# NRF52_CTAP_Authenticator.net
KiCad netlist of a schematic drawn in EAGLE
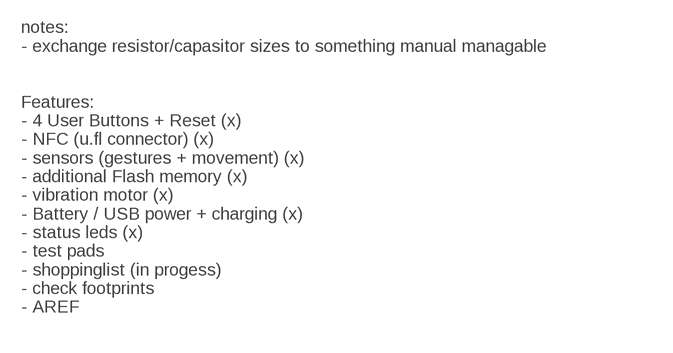
[diagram p0: schematic, sheet 1, part 1 of 2]
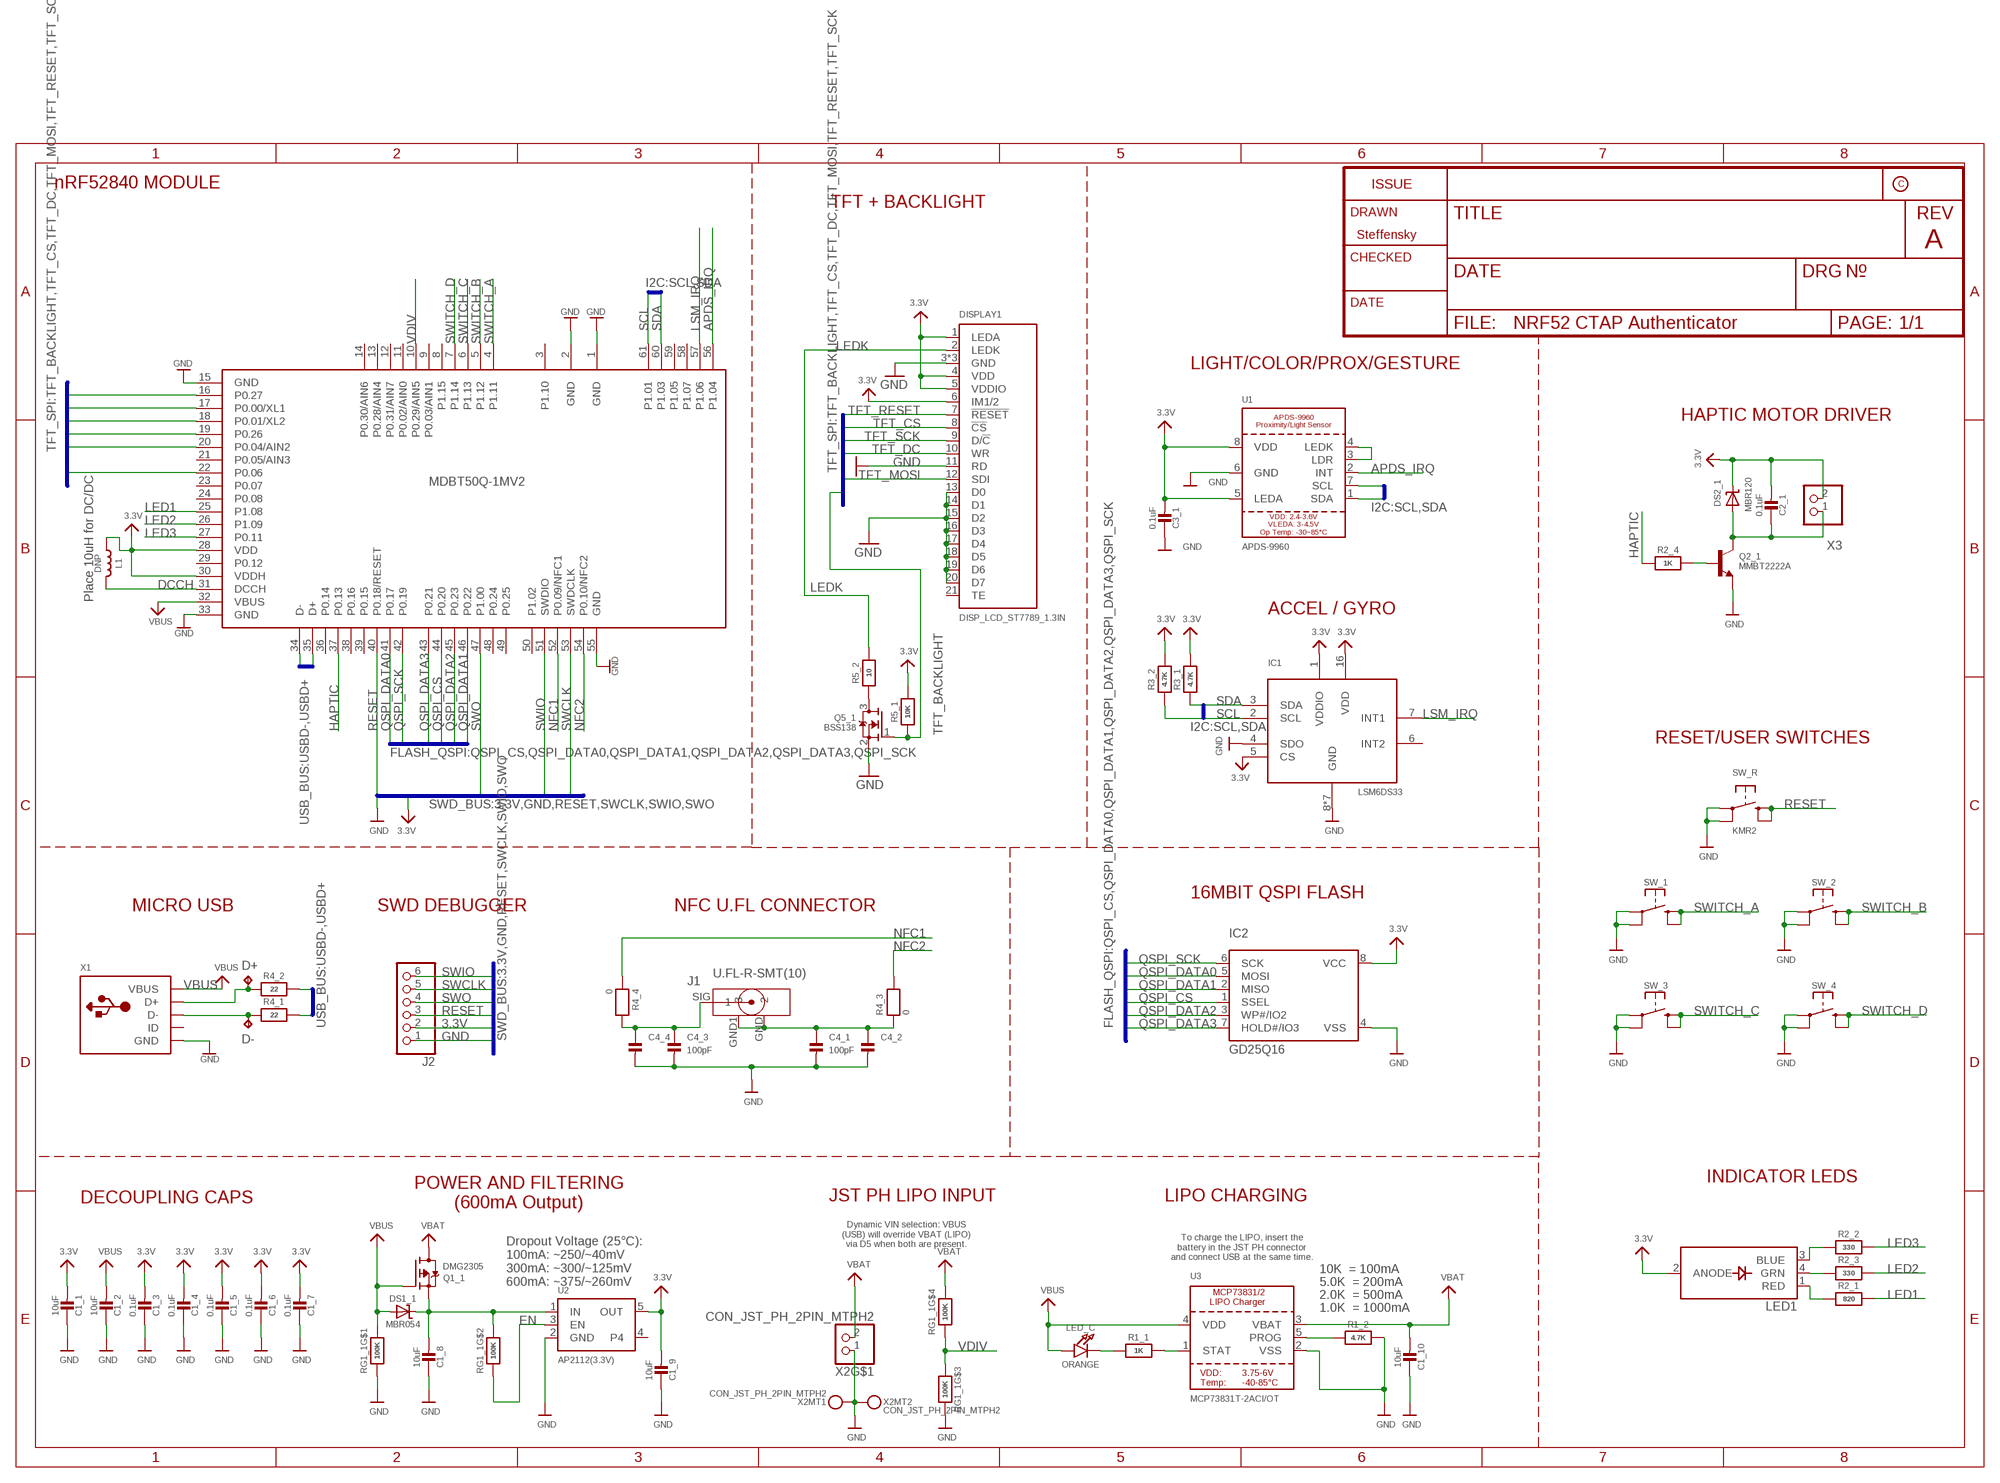
[diagram p1: schematic, sheet 1, part 2 of 2]

(export (version "E")
  (design (tool "Eeschema 10.0.6"))
  (components
    (comp (ref "C1_1")
      (value "10uF")
      (footprint "eagle-import:0805_NOTHERMALS")
      (libsource (lib "eagle-import") (part "CAP_CERAMIC0805-NOTHERMALS"))
    )
    (comp (ref "C1_2")
      (value "10uF")
      (footprint "eagle-import:0805_NOTHERMALS")
      (libsource (lib "eagle-import") (part "CAP_CERAMIC0805-NOTHERMALS"))
    )
    (comp (ref "C1_3")
      (value "0.1uF")
      (footprint "eagle-import:0805_NOTHERMALS")
      (libsource (lib "eagle-import") (part "CAP_CERAMIC0805-NOTHERMALS"))
    )
    (comp (ref "C1_4")
      (value "0.1uF")
      (footprint "eagle-import:0805_NOTHERMALS")
      (libsource (lib "eagle-import") (part "CAP_CERAMIC0805-NOTHERMALS"))
    )
    (comp (ref "C1_5")
      (value "0.1uF")
      (footprint "eagle-import:0805_NOTHERMALS")
      (libsource (lib "eagle-import") (part "CAP_CERAMIC0805-NOTHERMALS"))
    )
    (comp (ref "C1_6")
      (value "0.1uF")
      (footprint "eagle-import:0805_NOTHERMALS")
      (libsource (lib "eagle-import") (part "CAP_CERAMIC0805-NOTHERMALS"))
    )
    (comp (ref "C1_7")
      (value "0.1uF")
      (footprint "eagle-import:0805_NOTHERMALS")
      (libsource (lib "eagle-import") (part "CAP_CERAMIC0805-NOTHERMALS"))
    )
    (comp (ref "C1_8")
      (value "10uF")
      (footprint "eagle-import:0805_NOTHERMALS")
      (libsource (lib "eagle-import") (part "CAP_CERAMIC0805-NOTHERMALS"))
    )
    (comp (ref "C1_9")
      (value "10uF")
      (footprint "eagle-import:0805_NOTHERMALS")
      (libsource (lib "eagle-import") (part "CAP_CERAMIC0805-NOTHERMALS"))
    )
    (comp (ref "C1_10")
      (value "10uF")
      (footprint "eagle-import:0805_NOTHERMALS")
      (libsource (lib "eagle-import") (part "CAP_CERAMIC0805-NOTHERMALS"))
    )
    (comp (ref "C2_1")
      (value "0.1uF")
      (footprint "eagle-import:0805_NOTHERMALS")
      (libsource (lib "eagle-import") (part "CAP_CERAMIC0805-NOTHERMALS"))
    )
    (comp (ref "C3_1")
      (value "0.1uF")
      (footprint "eagle-import:0805_NOTHERMALS")
      (libsource (lib "eagle-import") (part "CAP_CERAMIC0805-NOTHERMALS"))
    )
    (comp (ref "C4_1")
      (value "100pF")
      (footprint "eagle-import:0805_NOTHERMALS")
      (libsource (lib "eagle-import") (part "CAP_CERAMIC0805-NOTHERMALS"))
    )
    (comp (ref "C4_2")
      (value "CAP_CERAMIC0805-NOTHERMALS")
      (footprint "eagle-import:0805_NOTHERMALS")
      (libsource (lib "eagle-import") (part "CAP_CERAMIC0805-NOTHERMALS"))
    )
    (comp (ref "C4_3")
      (value "100pF")
      (footprint "eagle-import:0805_NOTHERMALS")
      (libsource (lib "eagle-import") (part "CAP_CERAMIC0805-NOTHERMALS"))
    )
    (comp (ref "C4_4")
      (value "CAP_CERAMIC0805-NOTHERMALS")
      (footprint "eagle-import:0805_NOTHERMALS")
      (libsource (lib "eagle-import") (part "CAP_CERAMIC0805-NOTHERMALS"))
    )
    (comp (ref "D+")
      (value "TPTP10R")
      (footprint "eagle-import:TP10R")
      (libsource (lib "eagle-import") (part "TPTP10R"))
    )
    (comp (ref "D-")
      (value "TPTP10R")
      (footprint "eagle-import:TP10R")
      (libsource (lib "eagle-import") (part "TPTP10R"))
    )
    (comp (ref "DISPLAY1")
      (value "DISP_LCD_ST7789_1.3IN")
      (footprint "eagle-import:TFT_1.3IN_240X240_24P")
      (libsource (lib "eagle-import") (part "DISP_LCD_ST7789_1.3IN"))
    )
    (comp (ref "DS1_1")
      (value "MBR054")
      (footprint "eagle-import:SOD-123")
      (libsource (lib "eagle-import") (part "DIODE-SCHOTTKYSOD-123"))
    )
    (comp (ref "DS2_1")
      (value "MBR120")
      (footprint "eagle-import:SOD-123")
      (libsource (lib "eagle-import") (part "DIODE-SCHOTTKYSOD-123"))
    )
    (comp (ref "IC1")
      (value "LSM6DS33")
      (footprint "eagle-import:LGA16_3X3MM")
      (libsource (lib "eagle-import") (part "LSM6DS33"))
    )
    (comp (ref "IC2")
      (value "GD25Q16")
      (footprint "eagle-import:SOIC8_150MIL")
      (libsource (lib "eagle-import") (part "SPIFLASH_8PIN"))
    )
    (comp (ref "J1")
      (value "U.FL-R-SMT(10)")
      (footprint "eagle-import:U.FL-R-SMT(10)")
      (fields
        (field (name "DIGIKEY_PART_NUMBER") "H9161CT-ND")
        (field (name "MANUFACTURER") "Hirose Electric Co Ltd")
        (field (name "CREATED_BY") "PCBLayout.com")
      )
      (libsource (lib "eagle-import") (part "U.FL-R-SMT(10)"))
    )
    (comp (ref "J2")
      (value "HEADER-1X6ROUND")
      (footprint "eagle-import:1X06_ROUND")
      (libsource (lib "eagle-import") (part "HEADER-1X6ROUND"))
    )
    (comp (ref "L1")
      (value "DNP")
      (footprint "eagle-import:_0805MP")
      (libsource (lib "eagle-import") (part "INDUCTOR_0805MP"))
    )
    (comp (ref "LED1")
      (value "LED_RGB_PLCC4")
      (footprint "eagle-import:RGBLED_PLCC4")
      (libsource (lib "eagle-import") (part "LED_RGB_PLCC4"))
    )
    (comp (ref "LED_C")
      (value "ORANGE")
      (footprint "eagle-import:CHIPLED_0805_NOOUTLINE")
      (libsource (lib "eagle-import") (part "LED0805_NOOUTLINE"))
    )
    (comp (ref "MDBT50Q-1MV2")
      (value "MDBT50")
      (footprint "eagle-import:MDBT50")
      (libsource (lib "eagle-import") (part "MDBT50"))
    )
    (comp (ref "Q1_1")
      (value "DMG2305")
      (footprint "eagle-import:SOT23-R@1")
      (libsource (lib "eagle-import") (part "MOSFET-P"))
    )
    (comp (ref "Q2_1")
      (value "MMBT2222A")
      (footprint "eagle-import:SOT23-R")
      (libsource (lib "eagle-import") (part "TRANSISTOR_NPN"))
    )
    (comp (ref "Q5_1")
      (value "BSS138")
      (footprint "eagle-import:SOT23-WIDE")
      (libsource (lib "eagle-import") (part "MOSFET-NWIDE"))
    )
    (comp (ref "R1_1")
      (value "1K")
      (footprint "eagle-import:0805_NOTHERMALS")
      (libsource (lib "eagle-import") (part "RESISTOR0805_NOTHERMALS"))
    )
    (comp (ref "R1_2")
      (value "4.7K")
      (footprint "eagle-import:0805_NOTHERMALS")
      (libsource (lib "eagle-import") (part "RESISTOR0805_NOTHERMALS"))
    )
    (comp (ref "R2_1")
      (value "820")
      (footprint "eagle-import:0805_NOTHERMALS")
      (libsource (lib "eagle-import") (part "RESISTOR0805_NOTHERMALS"))
    )
    (comp (ref "R2_2")
      (value "330")
      (footprint "eagle-import:0805_NOTHERMALS")
      (libsource (lib "eagle-import") (part "RESISTOR0805_NOTHERMALS"))
    )
    (comp (ref "R2_3")
      (value "330")
      (footprint "eagle-import:0805_NOTHERMALS")
      (libsource (lib "eagle-import") (part "RESISTOR0805_NOTHERMALS"))
    )
    (comp (ref "R2_4")
      (value "1K")
      (footprint "eagle-import:0805_NOTHERMALS")
      (libsource (lib "eagle-import") (part "RESISTOR0805_NOTHERMALS"))
    )
    (comp (ref "R3_1")
      (value "4.7K")
      (footprint "eagle-import:0805_NOTHERMALS")
      (libsource (lib "eagle-import") (part "RESISTOR0805_NOTHERMALS"))
    )
    (comp (ref "R3_2")
      (value "4.7K")
      (footprint "eagle-import:0805_NOTHERMALS")
      (libsource (lib "eagle-import") (part "RESISTOR0805_NOTHERMALS"))
    )
    (comp (ref "R4_1")
      (value "22")
      (footprint "eagle-import:0805_NOTHERMALS")
      (libsource (lib "eagle-import") (part "RESISTOR0805_NOTHERMALS"))
    )
    (comp (ref "R4_2")
      (value "22")
      (footprint "eagle-import:0805_NOTHERMALS")
      (libsource (lib "eagle-import") (part "RESISTOR0805_NOTHERMALS"))
    )
    (comp (ref "R4_3")
      (value "0")
      (footprint "eagle-import:0805_NOTHERMALS")
      (libsource (lib "eagle-import") (part "RESISTOR0805_NOTHERMALS"))
    )
    (comp (ref "R4_4")
      (value "0")
      (footprint "eagle-import:0805_NOTHERMALS")
      (libsource (lib "eagle-import") (part "RESISTOR0805_NOTHERMALS"))
    )
    (comp (ref "R5_1")
      (value "10K")
      (footprint "eagle-import:0805_NOTHERMALS")
      (libsource (lib "eagle-import") (part "RESISTOR0805_NOTHERMALS"))
    )
    (comp (ref "R5_2")
      (value "10")
      (footprint "eagle-import:0805_NOTHERMALS")
      (libsource (lib "eagle-import") (part "RESISTOR0805_NOTHERMALS"))
    )
    (comp (ref "RG1_1")
      (value "100K")
      (footprint "eagle-import:RESPACK_4X0603")
      (libsource (lib "eagle-import") (part "RESISTOR_4PACK"))
    )
    (comp (ref "SW_1")
      (value "SWITCH_TACT_SMT_6MM")
      (footprint "eagle-import:6MMX6MM_TACTILE_SMT")
      (libsource (lib "eagle-import") (part "SWITCH_TACT_SMT_6MM"))
    )
    (comp (ref "SW_2")
      (value "SWITCH_TACT_SMT_6MM")
      (footprint "eagle-import:6MMX6MM_TACTILE_SMT")
      (libsource (lib "eagle-import") (part "SWITCH_TACT_SMT_6MM"))
    )
    (comp (ref "SW_3")
      (value "SWITCH_TACT_SMT_6MM")
      (footprint "eagle-import:6MMX6MM_TACTILE_SMT")
      (libsource (lib "eagle-import") (part "SWITCH_TACT_SMT_6MM"))
    )
    (comp (ref "SW_4")
      (value "SWITCH_TACT_SMT_6MM")
      (footprint "eagle-import:6MMX6MM_TACTILE_SMT")
      (libsource (lib "eagle-import") (part "SWITCH_TACT_SMT_6MM"))
    )
    (comp (ref "SW_R")
      (value "KMR2")
      (footprint "eagle-import:BTN_KMR2_4.6X2.8")
      (libsource (lib "eagle-import") (part "microbuilder_SWITCH_TACT_SMT4.6X2.8"))
    )
    (comp (ref "U1")
      (value "APDS-9960")
      (footprint "eagle-import:APDS-9960")
      (libsource (lib "eagle-import") (part "APDS-9960"))
    )
    (comp (ref "U2")
      (value "AP2112(3.3V)")
      (footprint "eagle-import:SOT23-5")
      (libsource (lib "eagle-import") (part "VREG_SOT23-5"))
    )
    (comp (ref "U3")
      (value "MCP73831T-2ACI/OT")
      (footprint "eagle-import:SOT23-5")
      (libsource (lib "eagle-import") (part "MCP73831/2"))
    )
    (comp (ref "X1")
      (value "USB_MICRO_20329_V2")
      (footprint "eagle-import:4UCONN_20329_V2")
      (libsource (lib "eagle-import") (part "USB_MICRO_20329_V2"))
    )
    (comp (ref "X2")
      (value "CON_JST_PH_2PIN_MTPH2")
      (footprint "eagle-import:JSTPH2")
      (libsource (lib "eagle-import") (part "CON_JST_PH_2PIN_MTPH2"))
    )
    (comp (ref "X3")
      (value "CON_JST_PH_2PINPH2_NOTHERMALS")
      (footprint "eagle-import:JSTPH2_NOTHERMALS")
      (libsource (lib "eagle-import") (part "CON_JST_PH_2PINPH2_NOTHERMALS"))
    )
  )
  (nets
    (net (code "6") (name "/APDS_IRQ") (class "Default")
      (node (ref "MDBT50Q-1MV2") (pin "56") (pinfunction "P1.04_56") (pintype "bidirectional"))
      (node (ref "U1") (pin "2") (pinfunction "INT_2") (pintype "output"))
    )
    (net (code "7") (name "/DCCH") (class "Default")
      (node (ref "L1") (pin "2") (pinfunction "2_2") (pintype "passive"))
      (node (ref "MDBT50Q-1MV2") (pin "31") (pinfunction "DCCH_31") (pintype "bidirectional"))
    )
    (net (code "8") (name "/EN") (class "Default")
      (node (ref "RG1_1") (pin "2") (pinfunction "1_2") (pintype "passive"))
      (node (ref "U2") (pin "3") (pinfunction "EN_3") (pintype "input"))
    )
    (net (code "9") (name "/HAPTIC") (class "Default")
      (node (ref "MDBT50Q-1MV2") (pin "37") (pinfunction "P0.13_37") (pintype "bidirectional"))
      (node (ref "R2_4") (pin "1") (pinfunction "1_1") (pintype "passive"))
    )
    (net (code "10") (name "/LED1") (class "Default")
      (node (ref "MDBT50Q-1MV2") (pin "25") (pinfunction "P1.08_25") (pintype "bidirectional"))
      (node (ref "R2_1") (pin "2") (pinfunction "2_2") (pintype "passive"))
    )
    (net (code "11") (name "/LED2") (class "Default")
      (node (ref "MDBT50Q-1MV2") (pin "26") (pinfunction "P1.09_26") (pintype "bidirectional"))
      (node (ref "R2_3") (pin "2") (pinfunction "2_2") (pintype "passive"))
    )
    (net (code "12") (name "/LED3") (class "Default")
      (node (ref "MDBT50Q-1MV2") (pin "27") (pinfunction "P0.11_27") (pintype "bidirectional"))
      (node (ref "R2_2") (pin "2") (pinfunction "2_2") (pintype "passive"))
    )
    (net (code "13") (name "/LEDK") (class "Default")
      (node (ref "DISPLAY1") (pin "2") (pinfunction "LEDK_2") (pintype "input"))
      (node (ref "R5_2") (pin "2") (pinfunction "2_2") (pintype "passive"))
    )
    (net (code "14") (name "/LSM_IRQ") (class "Default")
      (node (ref "IC1") (pin "7") (pinfunction "INT1_7") (pintype "output"))
      (node (ref "MDBT50Q-1MV2") (pin "57") (pinfunction "P1.06_57") (pintype "bidirectional"))
    )
    (net (code "15") (name "/NFC1") (class "Default")
      (node (ref "MDBT50Q-1MV2") (pin "52") (pinfunction "P0.09/NFC1_52") (pintype "bidirectional"))
      (node (ref "R4_4") (pin "1") (pinfunction "1_1") (pintype "passive"))
    )
    (net (code "16") (name "/NFC2") (class "Default")
      (node (ref "MDBT50Q-1MV2") (pin "54") (pinfunction "P0.10/NFC2_54") (pintype "bidirectional"))
      (node (ref "R4_3") (pin "2") (pinfunction "2_2") (pintype "passive"))
    )
    (net (code "17") (name "/QSPI_CS") (class "Default")
      (node (ref "IC2") (pin "1") (pinfunction "SSEL_1") (pintype "bidirectional"))
      (node (ref "MDBT50Q-1MV2") (pin "44") (pinfunction "P0.20_44") (pintype "bidirectional"))
    )
    (net (code "18") (name "/QSPI_DATA0") (class "Default")
      (node (ref "IC2") (pin "5") (pinfunction "MOSI_5") (pintype "bidirectional"))
      (node (ref "MDBT50Q-1MV2") (pin "41") (pinfunction "P0.17_41") (pintype "bidirectional"))
    )
    (net (code "19") (name "/QSPI_DATA1") (class "Default")
      (node (ref "IC2") (pin "2") (pinfunction "MISO_2") (pintype "bidirectional"))
      (node (ref "MDBT50Q-1MV2") (pin "46") (pinfunction "P0.22_46") (pintype "bidirectional"))
    )
    (net (code "20") (name "/QSPI_DATA2") (class "Default")
      (node (ref "IC2") (pin "3") (pinfunction "WP#/IO2_3") (pintype "bidirectional"))
      (node (ref "MDBT50Q-1MV2") (pin "45") (pinfunction "P0.23_45") (pintype "bidirectional"))
    )
    (net (code "21") (name "/QSPI_DATA3") (class "Default")
      (node (ref "IC2") (pin "7") (pinfunction "HOLD#/IO3_7") (pintype "bidirectional"))
      (node (ref "MDBT50Q-1MV2") (pin "43") (pinfunction "P0.21_43") (pintype "bidirectional"))
    )
    (net (code "22") (name "/QSPI_SCK") (class "Default")
      (node (ref "IC2") (pin "6") (pinfunction "SCK_6") (pintype "bidirectional"))
      (node (ref "MDBT50Q-1MV2") (pin "42") (pinfunction "P0.19_42") (pintype "bidirectional"))
    )
    (net (code "23") (name "/RESET") (class "Default")
      (node (ref "J2") (pin "3") (pinfunction "3_3") (pintype "passive"))
      (node (ref "MDBT50Q-1MV2") (pin "40") (pinfunction "P0.18/RESET_40") (pintype "bidirectional"))
      (node (ref "SW_R") (pin "B") (pinfunction "S_B") (pintype "passive"))
      (node (ref "SW_R") (pin "B'") (pinfunction "S1_B'") (pintype "passive"))
    )
    (net (code "24") (name "/SCL") (class "Default")
      (node (ref "IC1") (pin "2") (pinfunction "SCL_2") (pintype "bidirectional"))
      (node (ref "MDBT50Q-1MV2") (pin "61") (pinfunction "P1.01_61") (pintype "bidirectional"))
      (node (ref "R3_2") (pin "1") (pinfunction "1_1") (pintype "passive"))
      (node (ref "U1") (pin "7") (pinfunction "SCL_7") (pintype "input"))
    )
    (net (code "25") (name "/SDA") (class "Default")
      (node (ref "IC1") (pin "3") (pinfunction "SDA_3") (pintype "bidirectional"))
      (node (ref "MDBT50Q-1MV2") (pin "60") (pinfunction "P1.03_60") (pintype "bidirectional"))
      (node (ref "R3_1") (pin "1") (pinfunction "1_1") (pintype "passive"))
      (node (ref "U1") (pin "1") (pinfunction "SDA_1") (pintype "bidirectional"))
    )
    (net (code "26") (name "/SWCLK") (class "Default")
      (node (ref "J2") (pin "5") (pinfunction "5_5") (pintype "passive"))
      (node (ref "MDBT50Q-1MV2") (pin "53") (pinfunction "SWDCLK_53") (pintype "bidirectional"))
    )
    (net (code "27") (name "/SWIO") (class "Default")
      (node (ref "J2") (pin "6") (pinfunction "6_6") (pintype "passive"))
      (node (ref "MDBT50Q-1MV2") (pin "51") (pinfunction "SWDIO_51") (pintype "bidirectional"))
    )
    (net (code "28") (name "/SWITCH_A") (class "Default")
      (node (ref "MDBT50Q-1MV2") (pin "4") (pinfunction "P1.11_4") (pintype "bidirectional"))
      (node (ref "SW_1") (pin "B") (pinfunction "S_B") (pintype "passive"))
      (node (ref "SW_1") (pin "B'") (pinfunction "S1_B'") (pintype "passive"))
    )
    (net (code "29") (name "/SWITCH_B") (class "Default")
      (node (ref "MDBT50Q-1MV2") (pin "5") (pinfunction "P1.12_5") (pintype "bidirectional"))
      (node (ref "SW_2") (pin "B") (pinfunction "S_B") (pintype "passive"))
      (node (ref "SW_2") (pin "B'") (pinfunction "S1_B'") (pintype "passive"))
    )
    (net (code "30") (name "/SWITCH_C") (class "Default")
      (node (ref "MDBT50Q-1MV2") (pin "6") (pinfunction "P1.13_6") (pintype "bidirectional"))
      (node (ref "SW_3") (pin "B") (pinfunction "S_B") (pintype "passive"))
      (node (ref "SW_3") (pin "B'") (pinfunction "S1_B'") (pintype "passive"))
    )
    (net (code "31") (name "/SWITCH_D") (class "Default")
      (node (ref "MDBT50Q-1MV2") (pin "7") (pinfunction "P1.14_7") (pintype "bidirectional"))
      (node (ref "SW_4") (pin "B") (pinfunction "S_B") (pintype "passive"))
      (node (ref "SW_4") (pin "B'") (pinfunction "S1_B'") (pintype "passive"))
    )
    (net (code "32") (name "/SWO") (class "Default")
      (node (ref "J2") (pin "4") (pinfunction "4_4") (pintype "passive"))
      (node (ref "MDBT50Q-1MV2") (pin "47") (pinfunction "P1.00_47") (pintype "bidirectional"))
    )
    (net (code "33") (name "/TFT_BACKLIGHT") (class "Default")
      (node (ref "MDBT50Q-1MV2") (pin "16") (pinfunction "P0.27_16") (pintype "bidirectional"))
      (node (ref "Q5_1") (pin "1") (pinfunction "G_1") (pintype "bidirectional"))
      (node (ref "R5_1") (pin "1") (pinfunction "1_1") (pintype "passive"))
    )
    (net (code "34") (name "/TFT_CS") (class "Default")
      (node (ref "DISPLAY1") (pin "8") (pinfunction "~{CS}_8") (pintype "input"))
      (node (ref "MDBT50Q-1MV2") (pin "18") (pinfunction "P0.01/XL2_18") (pintype "bidirectional"))
    )
    (net (code "35") (name "/TFT_DC") (class "Default")
      (node (ref "DISPLAY1") (pin "10") (pinfunction "WR_10") (pintype "input"))
      (node (ref "MDBT50Q-1MV2") (pin "20") (pinfunction "P0.04/AIN2_20") (pintype "bidirectional"))
    )
    (net (code "36") (name "/TFT_MOSI") (class "Default")
      (node (ref "DISPLAY1") (pin "12") (pinfunction "SDI_12") (pintype "input"))
      (node (ref "MDBT50Q-1MV2") (pin "22") (pinfunction "P0.06_22") (pintype "bidirectional"))
    )
    (net (code "37") (name "/TFT_RESET") (class "Default")
      (node (ref "DISPLAY1") (pin "7") (pinfunction "~{RESET}_7") (pintype "input"))
      (node (ref "MDBT50Q-1MV2") (pin "17") (pinfunction "P0.00/XL1_17") (pintype "bidirectional"))
    )
    (net (code "38") (name "/TFT_SCK") (class "Default")
      (node (ref "DISPLAY1") (pin "9") (pinfunction "D/~{C}_9") (pintype "input"))
      (node (ref "MDBT50Q-1MV2") (pin "19") (pinfunction "P0.26_19") (pintype "bidirectional"))
    )
    (net (code "39") (name "/USBD+") (class "Default")
      (node (ref "MDBT50Q-1MV2") (pin "35") (pinfunction "D+_35") (pintype "bidirectional"))
      (node (ref "R4_2") (pin "2") (pinfunction "2_2") (pintype "passive"))
    )
    (net (code "40") (name "/USBD-") (class "Default")
      (node (ref "MDBT50Q-1MV2") (pin "34") (pinfunction "D-_34") (pintype "bidirectional"))
      (node (ref "R4_1") (pin "2") (pinfunction "2_2") (pintype "passive"))
    )
    (net (code "41") (name "/VDIV") (class "Default")
      (node (ref "MDBT50Q-1MV2") (pin "10") (pinfunction "P0.29/AIN5_10") (pintype "bidirectional"))
      (node (ref "RG1_1") (pin "3") (pinfunction "1_3") (pintype "passive"))
      (node (ref "RG1_1") (pin "4") (pinfunction "1_4") (pintype "passive"))
    )
    (net (code "47") (name "3.3V") (class "Default")
      (node (ref "C1_1") (pin "2") (pinfunction "P$2_2") (pintype "passive"))
      (node (ref "C1_3") (pin "2") (pinfunction "P$2_2") (pintype "passive"))
      (node (ref "C1_4") (pin "2") (pinfunction "P$2_2") (pintype "passive"))
      (node (ref "C1_5") (pin "2") (pinfunction "P$2_2") (pintype "passive"))
      (node (ref "C1_6") (pin "2") (pinfunction "P$2_2") (pintype "passive"))
      (node (ref "C1_7") (pin "2") (pinfunction "P$2_2") (pintype "passive"))
      (node (ref "C1_9") (pin "2") (pinfunction "P$2_2") (pintype "passive"))
      (node (ref "C2_1") (pin "2") (pinfunction "P$2_2") (pintype "passive"))
      (node (ref "C3_1") (pin "2") (pinfunction "P$2_2") (pintype "passive"))
      (node (ref "DISPLAY1") (pin "1") (pinfunction "LEDA_1") (pintype "input"))
      (node (ref "DISPLAY1") (pin "4") (pinfunction "VDD_4") (pintype "power_in"))
      (node (ref "DISPLAY1") (pin "5") (pinfunction "VDDIO_5") (pintype "power_in"))
      (node (ref "DISPLAY1") (pin "6") (pinfunction "IM1/2_6") (pintype "input"))
      (node (ref "DS2_1") (pin "C") (pinfunction "C_C") (pintype "passive"))
      (node (ref "IC1") (pin "1") (pinfunction "VDDIO_1") (pintype "power_in"))
      (node (ref "IC1") (pin "16") (pinfunction "VDD_16") (pintype "power_in"))
      (node (ref "IC1") (pin "5") (pinfunction "CS_5") (pintype "input"))
      (node (ref "IC2") (pin "8") (pinfunction "VCC_8") (pintype "bidirectional"))
      (node (ref "J2") (pin "2") (pinfunction "2_2") (pintype "passive"))
      (node (ref "L1") (pin "1") (pinfunction "1_1") (pintype "passive"))
      (node (ref "LED1") (pin "2") (pinfunction "ANODE_2") (pintype "power_in"))
      (node (ref "MDBT50Q-1MV2") (pin "28") (pinfunction "VDD_28") (pintype "bidirectional"))
      (node (ref "MDBT50Q-1MV2") (pin "30") (pinfunction "VDDH_30") (pintype "bidirectional"))
      (node (ref "R3_1") (pin "2") (pinfunction "2_2") (pintype "passive"))
      (node (ref "R3_2") (pin "2") (pinfunction "2_2") (pintype "passive"))
      (node (ref "R5_1") (pin "2") (pinfunction "2_2") (pintype "passive"))
      (node (ref "U1") (pin "5") (pinfunction "LEDA_5") (pintype "power_in"))
      (node (ref "U1") (pin "8") (pinfunction "VDD_8") (pintype "power_in"))
      (node (ref "U2") (pin "5") (pinfunction "OUT_5") (pintype "power_in"))
      (node (ref "X3") (pin "2") (pinfunction "2_2") (pintype "passive"))
    )
    (net (code "48") (name "GND") (class "Default")
      (node (ref "C1_1") (pin "1") (pinfunction "P$1_1") (pintype "passive"))
      (node (ref "C1_10") (pin "1") (pinfunction "P$1_1") (pintype "passive"))
      (node (ref "C1_2") (pin "1") (pinfunction "P$1_1") (pintype "passive"))
      (node (ref "C1_3") (pin "1") (pinfunction "P$1_1") (pintype "passive"))
      (node (ref "C1_4") (pin "1") (pinfunction "P$1_1") (pintype "passive"))
      (node (ref "C1_5") (pin "1") (pinfunction "P$1_1") (pintype "passive"))
      (node (ref "C1_6") (pin "1") (pinfunction "P$1_1") (pintype "passive"))
      (node (ref "C1_7") (pin "1") (pinfunction "P$1_1") (pintype "passive"))
      (node (ref "C1_8") (pin "1") (pinfunction "P$1_1") (pintype "passive"))
      (node (ref "C1_9") (pin "1") (pinfunction "P$1_1") (pintype "passive"))
      (node (ref "C3_1") (pin "1") (pinfunction "P$1_1") (pintype "passive"))
      (node (ref "C4_1") (pin "2") (pinfunction "P$2_2") (pintype "passive"))
      (node (ref "C4_2") (pin "2") (pinfunction "P$2_2") (pintype "passive"))
      (node (ref "C4_3") (pin "2") (pinfunction "P$2_2") (pintype "passive"))
      (node (ref "C4_4") (pin "2") (pinfunction "P$2_2") (pintype "passive"))
      (node (ref "DISPLAY1") (pin "11") (pinfunction "RD_11") (pintype "input"))
      (node (ref "DISPLAY1") (pin "13") (pinfunction "D0_13") (pintype "bidirectional"))
      (node (ref "DISPLAY1") (pin "14") (pinfunction "D1_14") (pintype "bidirectional"))
      (node (ref "DISPLAY1") (pin "15") (pinfunction "D2_15") (pintype "bidirectional"))
      (node (ref "DISPLAY1") (pin "16") (pinfunction "D3_16") (pintype "bidirectional"))
      (node (ref "DISPLAY1") (pin "17") (pinfunction "D4_17") (pintype "bidirectional"))
      (node (ref "DISPLAY1") (pin "18") (pinfunction "D5_18") (pintype "bidirectional"))
      (node (ref "DISPLAY1") (pin "19") (pinfunction "D6_19") (pintype "bidirectional"))
      (node (ref "DISPLAY1") (pin "20") (pinfunction "D7_20") (pintype "bidirectional"))
      (node (ref "DISPLAY1") (pin "23") (pinfunction "GND_23") (pintype "power_in"))
      (node (ref "DISPLAY1") (pin "24") (pinfunction "GND_24") (pintype "power_in"))
      (node (ref "DISPLAY1") (pin "3") (pinfunction "GND_3") (pintype "power_in"))
      (node (ref "IC1") (pin "10") (pinfunction "GND_10") (pintype "power_in"))
      (node (ref "IC1") (pin "11") (pinfunction "GND_11") (pintype "power_in"))
      (node (ref "IC1") (pin "12") (pinfunction "GND_12") (pintype "power_in"))
      (node (ref "IC1") (pin "13") (pinfunction "GND_13") (pintype "power_in"))
      (node (ref "IC1") (pin "15") (pinfunction "GND_15") (pintype "power_in"))
      (node (ref "IC1") (pin "4") (pinfunction "SDO_4") (pintype "bidirectional"))
      (node (ref "IC1") (pin "8") (pinfunction "GND_8") (pintype "power_in"))
      (node (ref "IC1") (pin "9") (pinfunction "GND_9") (pintype "power_in"))
      (node (ref "IC2") (pin "4") (pinfunction "VSS_4") (pintype "bidirectional"))
      (node (ref "J2") (pin "1") (pinfunction "1_1") (pintype "passive"))
      (node (ref "MDBT50Q-1MV2") (pin "1") (pinfunction "GND_1") (pintype "bidirectional"))
      (node (ref "MDBT50Q-1MV2") (pin "15") (pinfunction "GND_15") (pintype "bidirectional"))
      (node (ref "MDBT50Q-1MV2") (pin "2") (pinfunction "GND_2") (pintype "bidirectional"))
      (node (ref "MDBT50Q-1MV2") (pin "33") (pinfunction "GND_33") (pintype "bidirectional"))
      (node (ref "MDBT50Q-1MV2") (pin "55") (pinfunction "GND_55") (pintype "bidirectional"))
      (node (ref "Q2_1") (pin "2") (pinfunction "E_2") (pintype "passive"))
      (node (ref "Q5_1") (pin "2") (pinfunction "S_2") (pintype "bidirectional"))
      (node (ref "R1_2") (pin "2") (pinfunction "2_2") (pintype "passive"))
      (node (ref "RG1_1") (pin "1") (pinfunction "1_1") (pintype "passive"))
      (node (ref "RG1_1") (pin "6") (pinfunction "2_6") (pintype "passive"))
      (node (ref "SW_1") (pin "A") (pinfunction "P_A") (pintype "passive"))
      (node (ref "SW_1") (pin "A'") (pinfunction "P1_A'") (pintype "passive"))
      (node (ref "SW_2") (pin "A") (pinfunction "P_A") (pintype "passive"))
      (node (ref "SW_2") (pin "A'") (pinfunction "P1_A'") (pintype "passive"))
      (node (ref "SW_3") (pin "A") (pinfunction "P_A") (pintype "passive"))
      (node (ref "SW_3") (pin "A'") (pinfunction "P1_A'") (pintype "passive"))
      (node (ref "SW_4") (pin "A") (pinfunction "P_A") (pintype "passive"))
      (node (ref "SW_4") (pin "A'") (pinfunction "P1_A'") (pintype "passive"))
      (node (ref "SW_R") (pin "A") (pinfunction "P_A") (pintype "passive"))
      (node (ref "SW_R") (pin "A'") (pinfunction "P1_A'") (pintype "passive"))
      (node (ref "U1") (pin "6") (pinfunction "GND_6") (pintype "power_in"))
      (node (ref "U2") (pin "2") (pinfunction "GND_2") (pintype "power_in"))
      (node (ref "U3") (pin "2") (pinfunction "VSS_2") (pintype "power_in"))
      (node (ref "X1") (pin "BASE@1") (pinfunction "GND_BASE@1") (pintype "power_in"))
      (node (ref "X1") (pin "BASE@2") (pinfunction "GND_BASE@2") (pintype "power_in"))
      (node (ref "X1") (pin "GND") (pinfunction "GND_GND") (pintype "power_in"))
      (node (ref "X1") (pin "SPRT@1") (pinfunction "GND_SPRT@1") (pintype "power_in"))
      (node (ref "X1") (pin "SPRT@2") (pinfunction "GND_SPRT@2") (pintype "power_in"))
      (node (ref "X1") (pin "SPRT@3") (pinfunction "GND_SPRT@3") (pintype "power_in"))
      (node (ref "X1") (pin "SPRT@4") (pinfunction "GND_SPRT@4") (pintype "power_in"))
      (node (ref "X2") (pin "1") (pinfunction "1_1") (pintype "passive"))
      (node (ref "X2") (pin "NC1") (pinfunction "P$1_NC1") (pintype "bidirectional"))
      (node (ref "X2") (pin "NC2") (pinfunction "P$1_NC2") (pintype "bidirectional"))
    )
    (net (code "49") (name "Net-(C1_8-P$2)") (class "Default")
      (node (ref "C1_8") (pin "2") (pinfunction "P$2_2") (pintype "passive"))
      (node (ref "DS1_1") (pin "C") (pinfunction "C_C") (pintype "passive"))
      (node (ref "Q1_1") (pin "2") (pinfunction "S_2") (pintype "passive"))
      (node (ref "RG1_1") (pin "7") (pinfunction "2_7") (pintype "passive"))
      (node (ref "U2") (pin "1") (pinfunction "IN_1") (pintype "power_in"))
    )
    (net (code "50") (name "Net-(C2_1-P$1)") (class "Default")
      (node (ref "C2_1") (pin "1") (pinfunction "P$1_1") (pintype "passive"))
      (node (ref "DS2_1") (pin "A") (pinfunction "A_A") (pintype "passive"))
      (node (ref "Q2_1") (pin "3") (pinfunction "C_3") (pintype "passive"))
      (node (ref "X3") (pin "1") (pinfunction "1_1") (pintype "passive"))
    )
    (net (code "51") (name "Net-(C4_1-P$1)") (class "Default")
      (node (ref "C4_1") (pin "1") (pinfunction "P$1_1") (pintype "passive"))
      (node (ref "C4_2") (pin "1") (pinfunction "P$1_1") (pintype "passive"))
      (node (ref "J1") (pin "GND") (pinfunction "2_GND") (pintype "passive"))
      (node (ref "J1") (pin "GND1") (pinfunction "3_GND1") (pintype "passive"))
      (node (ref "R4_3") (pin "1") (pinfunction "1_1") (pintype "passive"))
    )
    (net (code "52") (name "Net-(C4_3-P$1)") (class "Default")
      (node (ref "C4_3") (pin "1") (pinfunction "P$1_1") (pintype "passive"))
      (node (ref "C4_4") (pin "1") (pinfunction "P$1_1") (pintype "passive"))
      (node (ref "J1") (pin "SIG") (pinfunction "1_SIG") (pintype "passive"))
      (node (ref "R4_4") (pin "2") (pinfunction "2_2") (pintype "passive"))
    )
    (net (code "53") (name "Net-(D+-PadTP)") (class "Default")
      (node (ref "D+") (pin "TP") (pinfunction "TP_TP") (pintype "input"))
      (node (ref "R4_2") (pin "1") (pinfunction "1_1") (pintype "passive"))
      (node (ref "X1") (pin "D+") (pinfunction "D+_D+") (pintype "bidirectional"))
    )
    (net (code "54") (name "Net-(D--PadTP)") (class "Default")
      (node (ref "D-") (pin "TP") (pinfunction "TP_TP") (pintype "input"))
      (node (ref "R4_1") (pin "1") (pinfunction "1_1") (pintype "passive"))
      (node (ref "X1") (pin "D-") (pinfunction "D-_D-") (pintype "bidirectional"))
    )
    (net (code "55") (name "Net-(LED1-BLUE)") (class "Default")
      (node (ref "LED1") (pin "3") (pinfunction "BLUE_3") (pintype "bidirectional"))
      (node (ref "R2_2") (pin "1") (pinfunction "1_1") (pintype "passive"))
    )
    (net (code "56") (name "Net-(LED1-GRN)") (class "Default")
      (node (ref "LED1") (pin "4") (pinfunction "GRN_4") (pintype "bidirectional"))
      (node (ref "R2_3") (pin "1") (pinfunction "1_1") (pintype "passive"))
    )
    (net (code "57") (name "Net-(LED1-RED)") (class "Default")
      (node (ref "LED1") (pin "1") (pinfunction "RED_1") (pintype "bidirectional"))
      (node (ref "R2_1") (pin "1") (pinfunction "1_1") (pintype "passive"))
    )
    (net (code "58") (name "Net-(LED_C-PadC)") (class "Default")
      (node (ref "LED_C") (pin "C") (pinfunction "C_C") (pintype "passive"))
      (node (ref "R1_1") (pin "1") (pinfunction "1_1") (pintype "passive"))
    )
    (net (code "59") (name "Net-(Q2_1-B)") (class "Default")
      (node (ref "Q2_1") (pin "1") (pinfunction "B_1") (pintype "passive"))
      (node (ref "R2_4") (pin "2") (pinfunction "2_2") (pintype "passive"))
    )
    (net (code "60") (name "Net-(Q5_1-D)") (class "Default")
      (node (ref "Q5_1") (pin "3") (pinfunction "D_3") (pintype "bidirectional"))
      (node (ref "R5_2") (pin "1") (pinfunction "1_1") (pintype "passive"))
    )
    (net (code "61") (name "Net-(U1-LDR)") (class "Default")
      (node (ref "U1") (pin "3") (pinfunction "LDR_3") (pintype "bidirectional"))
      (node (ref "U1") (pin "4") (pinfunction "LEDK_4") (pintype "bidirectional"))
    )
    (net (code "62") (name "Net-(U3-PROG)") (class "Default")
      (node (ref "R1_2") (pin "1") (pinfunction "1_1") (pintype "passive"))
      (node (ref "U3") (pin "5") (pinfunction "PROG_5") (pintype "input"))
    )
    (net (code "63") (name "Net-(U3-STAT)") (class "Default")
      (node (ref "R1_1") (pin "2") (pinfunction "2_2") (pintype "passive"))
      (node (ref "U3") (pin "1") (pinfunction "STAT_1") (pintype "output"))
    )
    (net (code "64") (name "VBAT") (class "Default")
      (node (ref "C1_10") (pin "2") (pinfunction "P$2_2") (pintype "passive"))
      (node (ref "Q1_1") (pin "3") (pinfunction "D_3") (pintype "passive"))
      (node (ref "RG1_1") (pin "5") (pinfunction "2_5") (pintype "passive"))
      (node (ref "U3") (pin "3") (pinfunction "VBAT_3") (pintype "power_in"))
      (node (ref "X2") (pin "2") (pinfunction "2_2") (pintype "passive"))
    )
    (net (code "65") (name "VBUS") (class "Default")
      (node (ref "C1_2") (pin "2") (pinfunction "P$2_2") (pintype "passive"))
      (node (ref "DS1_1") (pin "A") (pinfunction "A_A") (pintype "passive"))
      (node (ref "LED_C") (pin "A") (pinfunction "A_A") (pintype "passive"))
      (node (ref "MDBT50Q-1MV2") (pin "32") (pinfunction "VBUS_32") (pintype "bidirectional"))
      (node (ref "Q1_1") (pin "1") (pinfunction "G_1") (pintype "passive"))
      (node (ref "RG1_1") (pin "8") (pinfunction "2_8") (pintype "passive"))
      (node (ref "U3") (pin "4") (pinfunction "VDD_4") (pintype "power_in"))
      (node (ref "X1") (pin "VBUS") (pinfunction "VBUS_VBUS") (pintype "power_in"))
    )
    (net (code "66") (name "unconnected-(DISPLAY1-TE-Pad21)") (class "Default")
      (node (ref "DISPLAY1") (pin "21") (pinfunction "TE_21") (pintype "output"))
    )
    (net (code "67") (name "unconnected-(IC1-INT2-Pad6)") (class "Default")
      (node (ref "IC1") (pin "6") (pinfunction "INT2_6") (pintype "output"))
    )
    (net (code "68") (name "unconnected-(MDBT50Q-1MV2-P0.02{slash}AIN0-Pad11)") (class "Default")
      (node (ref "MDBT50Q-1MV2") (pin "11") (pinfunction "P0.02/AIN0_11") (pintype "bidirectional"))
    )
    (net (code "69") (name "unconnected-(MDBT50Q-1MV2-P0.03{slash}AIN1-Pad9)") (class "Default")
      (node (ref "MDBT50Q-1MV2") (pin "9") (pinfunction "P0.03/AIN1_9") (pintype "bidirectional"))
    )
    (net (code "70") (name "unconnected-(MDBT50Q-1MV2-P0.05{slash}AIN3-Pad21)") (class "Default")
      (node (ref "MDBT50Q-1MV2") (pin "21") (pinfunction "P0.05/AIN3_21") (pintype "bidirectional"))
    )
    (net (code "71") (name "unconnected-(MDBT50Q-1MV2-P0.07-Pad23)") (class "Default")
      (node (ref "MDBT50Q-1MV2") (pin "23") (pinfunction "P0.07_23") (pintype "bidirectional"))
    )
    (net (code "72") (name "unconnected-(MDBT50Q-1MV2-P0.08-Pad24)") (class "Default")
      (node (ref "MDBT50Q-1MV2") (pin "24") (pinfunction "P0.08_24") (pintype "bidirectional"))
    )
    (net (code "73") (name "unconnected-(MDBT50Q-1MV2-P0.12-Pad29)") (class "Default")
      (node (ref "MDBT50Q-1MV2") (pin "29") (pinfunction "P0.12_29") (pintype "bidirectional"))
    )
    (net (code "74") (name "unconnected-(MDBT50Q-1MV2-P0.14-Pad36)") (class "Default")
      (node (ref "MDBT50Q-1MV2") (pin "36") (pinfunction "P0.14_36") (pintype "bidirectional"))
    )
    (net (code "75") (name "unconnected-(MDBT50Q-1MV2-P0.15-Pad39)") (class "Default")
      (node (ref "MDBT50Q-1MV2") (pin "39") (pinfunction "P0.15_39") (pintype "bidirectional"))
    )
    (net (code "76") (name "unconnected-(MDBT50Q-1MV2-P0.16-Pad38)") (class "Default")
      (node (ref "MDBT50Q-1MV2") (pin "38") (pinfunction "P0.16_38") (pintype "bidirectional"))
    )
    (net (code "77") (name "unconnected-(MDBT50Q-1MV2-P0.24-Pad48)") (class "Default")
      (node (ref "MDBT50Q-1MV2") (pin "48") (pinfunction "P0.24_48") (pintype "bidirectional"))
    )
    (net (code "78") (name "unconnected-(MDBT50Q-1MV2-P0.25-Pad49)") (class "Default")
      (node (ref "MDBT50Q-1MV2") (pin "49") (pinfunction "P0.25_49") (pintype "bidirectional"))
    )
    (net (code "79") (name "unconnected-(MDBT50Q-1MV2-P0.28{slash}AIN4-Pad13)") (class "Default")
      (node (ref "MDBT50Q-1MV2") (pin "13") (pinfunction "P0.28/AIN4_13") (pintype "bidirectional"))
    )
    (net (code "80") (name "unconnected-(MDBT50Q-1MV2-P0.30{slash}AIN6-Pad14)") (class "Default")
      (node (ref "MDBT50Q-1MV2") (pin "14") (pinfunction "P0.30/AIN6_14") (pintype "bidirectional"))
    )
    (net (code "81") (name "unconnected-(MDBT50Q-1MV2-P0.31{slash}AIN7-Pad12)") (class "Default")
      (node (ref "MDBT50Q-1MV2") (pin "12") (pinfunction "P0.31/AIN7_12") (pintype "bidirectional"))
    )
    (net (code "82") (name "unconnected-(MDBT50Q-1MV2-P1.02-Pad50)") (class "Default")
      (node (ref "MDBT50Q-1MV2") (pin "50") (pinfunction "P1.02_50") (pintype "bidirectional"))
    )
    (net (code "83") (name "unconnected-(MDBT50Q-1MV2-P1.05-Pad59)") (class "Default")
      (node (ref "MDBT50Q-1MV2") (pin "59") (pinfunction "P1.05_59") (pintype "bidirectional"))
    )
    (net (code "84") (name "unconnected-(MDBT50Q-1MV2-P1.07-Pad58)") (class "Default")
      (node (ref "MDBT50Q-1MV2") (pin "58") (pinfunction "P1.07_58") (pintype "bidirectional"))
    )
    (net (code "85") (name "unconnected-(MDBT50Q-1MV2-P1.10-Pad3)") (class "Default")
      (node (ref "MDBT50Q-1MV2") (pin "3") (pinfunction "P1.10_3") (pintype "bidirectional"))
    )
    (net (code "86") (name "unconnected-(MDBT50Q-1MV2-P1.15-Pad8)") (class "Default")
      (node (ref "MDBT50Q-1MV2") (pin "8") (pinfunction "P1.15_8") (pintype "bidirectional"))
    )
    (net (code "87") (name "unconnected-(U2-P4-Pad4)") (class "Default")
      (node (ref "U2") (pin "4") (pinfunction "P4_4") (pintype "bidirectional"))
    )
    (net (code "88") (name "unconnected-(X1-PadID)") (class "Default")
      (node (ref "X1") (pin "ID") (pinfunction "ID_ID") (pintype "bidirectional"))
    )
  )
)
